# STM32F407VG.net
KiCad netlist of a schematic drawn in Altium Designer
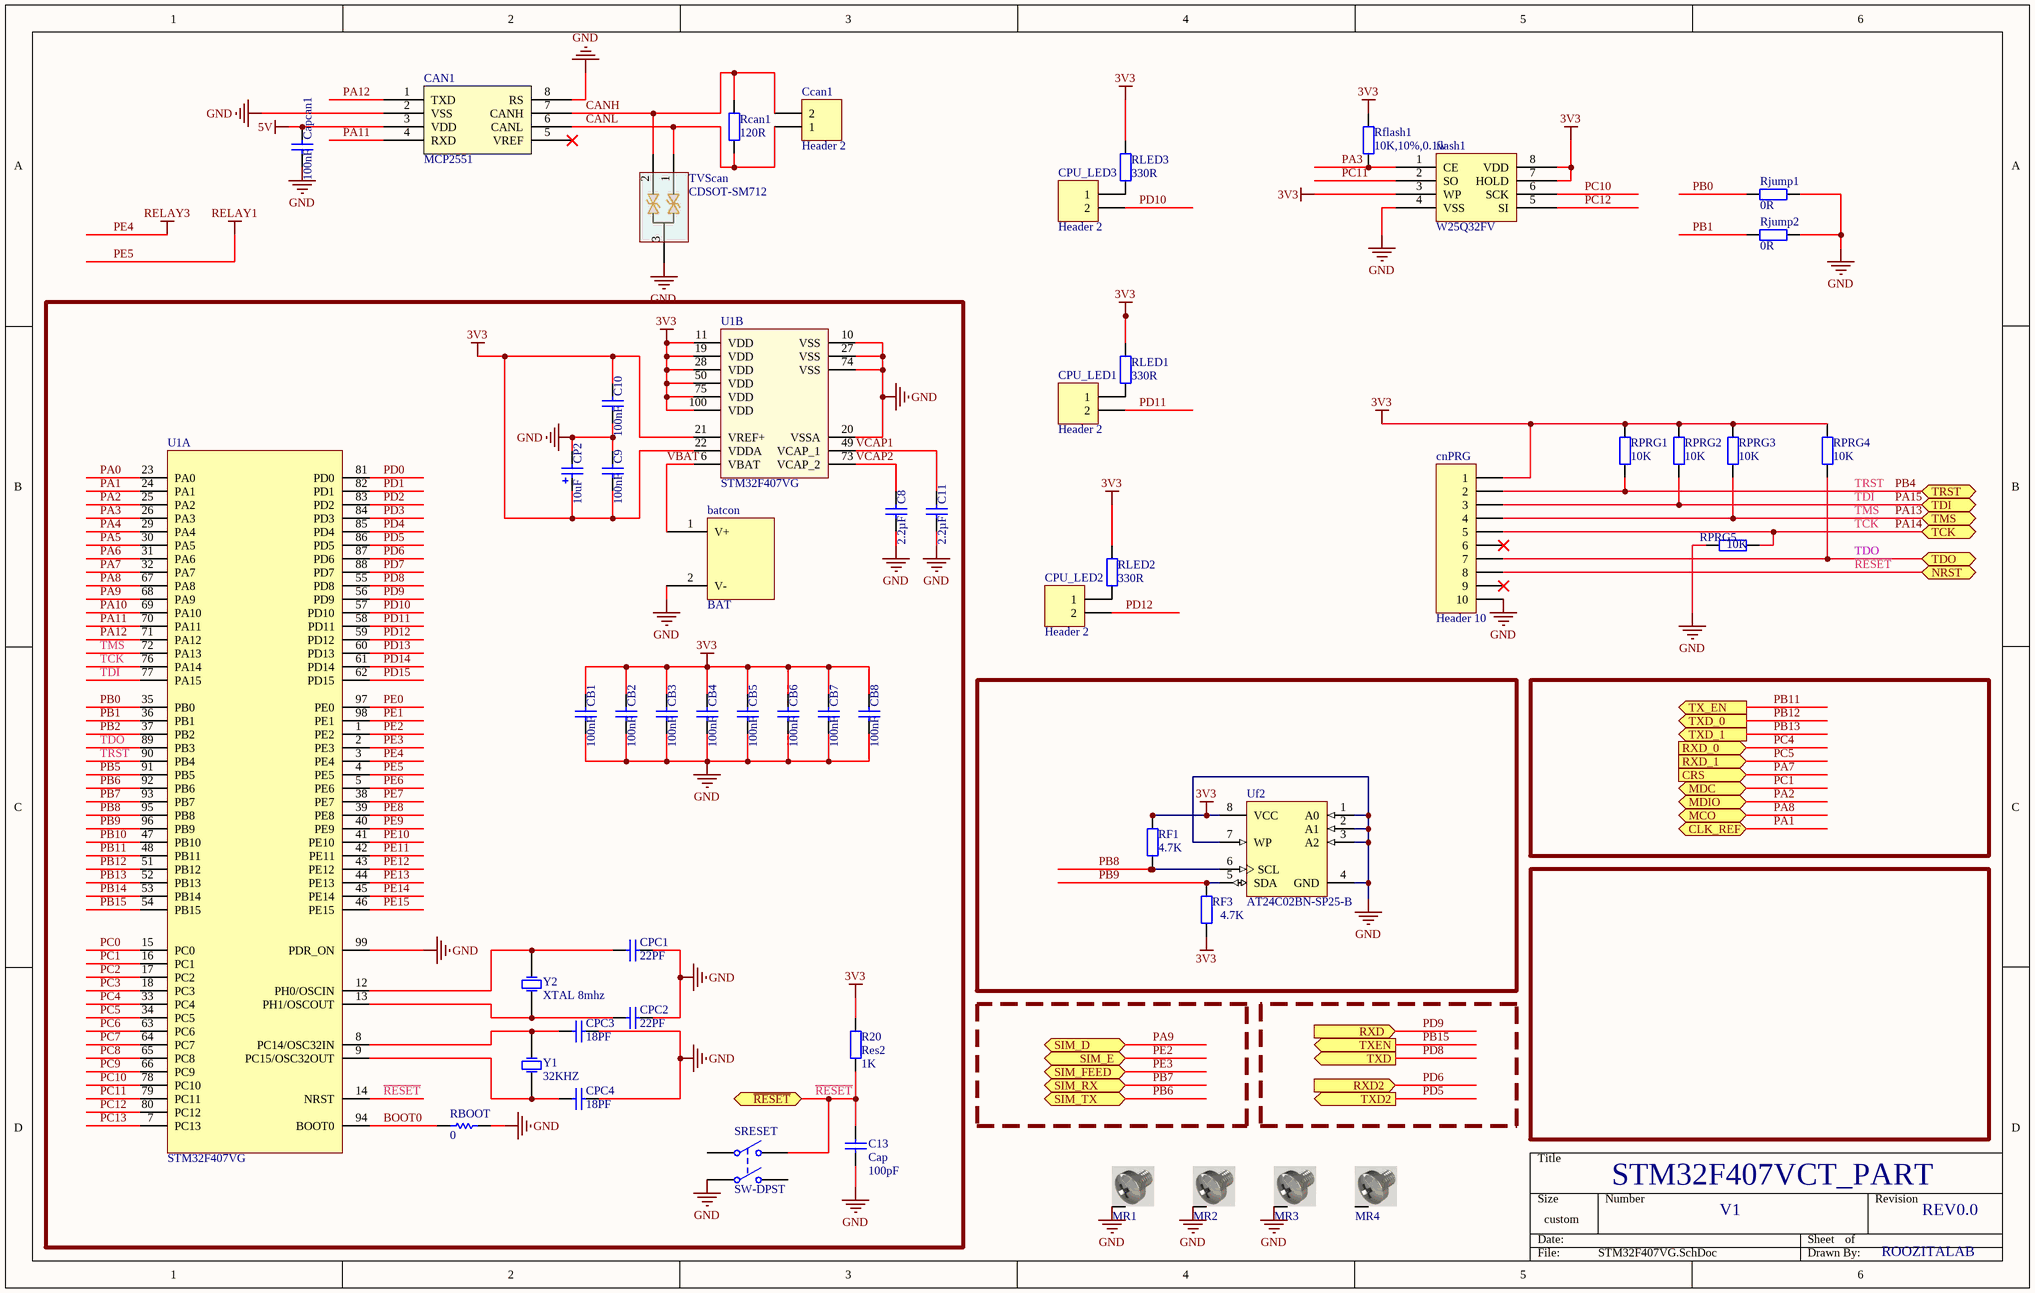
[diagram p0: STM32F407VG.SchDoc]

(export (version "E")
  (design (tool "Eeschema 10.0.6"))
  (components
    (comp (ref "batcon") (value "BAT") (footprint "BATTERY") (libsource (lib "my dxp lib") (part "BAT")))
    (comp (ref "C8")
      (value "2.2µF")
      (footprint "0805.")
      (description "Capacitor")
      (fields (field (name "PUBLISHER") "Altium Limited"))
      (libsource (lib "STM32F407_144") (part "Cap"))
    )
    (comp (ref "C9")
      (value "100nF")
      (footprint "0805.")
      (description "Capacitor")
      (fields (field (name "PUBLISHER") "Altium Limited"))
      (libsource (lib "STM32F407_144") (part "Cap"))
    )
    (comp (ref "C10")
      (value "100nF")
      (footprint "0805.")
      (description "Capacitor")
      (fields (field (name "PUBLISHER") "Altium Limited"))
      (libsource (lib "STM32F407_144") (part "Cap"))
    )
    (comp (ref "C11")
      (value "2.2µF")
      (footprint "0805.")
      (description "Capacitor")
      (fields (field (name "PUBLISHER") "Altium Limited"))
      (libsource (lib "STM32F407_144") (part "Cap"))
    )
    (comp (ref "C13")
      (value "Cap")
      (footprint "0805.")
      (description "Capacitor")
      (fields (field (name "ALTIUM_VALUE") "100pF") (field (name "PUBLISHER") "Altium Limited"))
      (libsource (lib "Miscellaneous Devices") (part "Cap"))
    )
    (comp (ref "CAN1")
      (value "MCP2551")
      (footprint "SOIC8")
      (libsource (lib "PCB_Project1") (part "SN65VHD230"))
    )
    (comp (ref "Capcan1")
      (value "100nF")
      (footprint "0805.")
      (description "Capacitor")
      (fields (field (name "PUBLISHER") "Altium Limited"))
      (libsource (lib "STM32F407_144") (part "Cap"))
    )
    (comp (ref "CB1")
      (value "100nF")
      (footprint "0805.")
      (description "Capacitor")
      (fields (field (name "PUBLISHER") "Altium Limited"))
      (libsource (lib "STM32F407_144") (part "Cap"))
    )
    (comp (ref "CB2")
      (value "100nF")
      (footprint "0805.")
      (description "Capacitor")
      (fields (field (name "PUBLISHER") "Altium Limited"))
      (libsource (lib "STM32F407_144") (part "Cap"))
    )
    (comp (ref "CB3")
      (value "100nF")
      (footprint "0805.")
      (description "Capacitor")
      (fields (field (name "PUBLISHER") "Altium Limited"))
      (libsource (lib "STM32F407_144") (part "Cap"))
    )
    (comp (ref "CB4")
      (value "100nF")
      (footprint "0805.")
      (description "Capacitor")
      (fields (field (name "PUBLISHER") "Altium Limited"))
      (libsource (lib "STM32F407_144") (part "Cap"))
    )
    (comp (ref "CB5")
      (value "100nF")
      (footprint "0805.")
      (description "Capacitor")
      (fields (field (name "PUBLISHER") "Altium Limited"))
      (libsource (lib "STM32F407_144") (part "Cap"))
    )
    (comp (ref "CB6")
      (value "100nF")
      (footprint "0805.")
      (description "Capacitor")
      (fields (field (name "PUBLISHER") "Altium Limited"))
      (libsource (lib "STM32F407_144") (part "Cap"))
    )
    (comp (ref "CB7")
      (value "100nF")
      (footprint "0805.")
      (description "Capacitor")
      (fields (field (name "PUBLISHER") "Altium Limited"))
      (libsource (lib "STM32F407_144") (part "Cap"))
    )
    (comp (ref "CB8")
      (value "100nF")
      (footprint "0805.")
      (description "Capacitor")
      (fields (field (name "PUBLISHER") "Altium Limited"))
      (libsource (lib "STM32F407_144") (part "Cap"))
    )
    (comp (ref "Ccan1")
      (value "Header 2")
      (footprint "HDR1X2")
      (description "Header, 2-Pin")
      (fields (field (name "PUBLISHER") "Altium Limited"))
      (libsource (lib "") (part "Header 2_1"))
    )
    (comp (ref "cnPRG")
      (value "Header 10")
      (footprint "HDR1X10")
      (description "Header, 10-Pin")
      (fields (field (name "PUBLISHER") "Altium Limited"))
      (libsource (lib "Miscellaneous Connectors") (part "Header 10"))
    )
    (comp (ref "CP2")
      (value "10uF")
      (footprint "C1206.")
      (description "Polarized Capacitor (Radial)")
      (fields (field (name "PUBLISHER") "Altium Limited"))
      (libsource (lib "STM32F407_144") (part "Cap Pol1"))
    )
    (comp (ref "CPC1")
      (value "22PF")
      (footprint "0805.")
      (description "Capacitor")
      (fields (field (name "PUBLISHER") "Altium Limited"))
      (libsource (lib "STM32F407VG") (part "Cap"))
    )
    (comp (ref "CPC2")
      (value "22PF")
      (footprint "0805.")
      (description "Capacitor")
      (fields (field (name "PUBLISHER") "Altium Limited"))
      (libsource (lib "STM32F407VG") (part "Cap"))
    )
    (comp (ref "CPC3")
      (value "18PF")
      (footprint "0805.")
      (description "Capacitor")
      (fields (field (name "PUBLISHER") "Altium Limited"))
      (libsource (lib "STM32F407VG") (part "Cap"))
    )
    (comp (ref "CPC4")
      (value "18PF")
      (footprint "0805.")
      (description "Capacitor")
      (fields (field (name "PUBLISHER") "Altium Limited"))
      (libsource (lib "STM32F407VG") (part "Cap"))
    )
    (comp (ref "CPU_LED1")
      (value "Header 2")
      (footprint "HDR1X2")
      (description "Header, 2-Pin")
      (fields (field (name "PUBLISHER") "Altium Limited"))
      (libsource (lib "Miscellaneous Connectors") (part "Header 2"))
    )
    (comp (ref "CPU_LED2")
      (value "Header 2")
      (footprint "HDR1X2")
      (description "Header, 2-Pin")
      (fields (field (name "PUBLISHER") "Altium Limited"))
      (libsource (lib "Miscellaneous Connectors") (part "Header 2"))
    )
    (comp (ref "CPU_LED3")
      (value "Header 2")
      (footprint "HDR1X2")
      (description "Header, 2-Pin")
      (fields (field (name "PUBLISHER") "Altium Limited"))
      (libsource (lib "Miscellaneous Connectors") (part "Header 2"))
    )
    (comp (ref "flash1")
      (value "W25Q32FV")
      (footprint "SOIC8")
      (libsource (lib "PCB_Project1") (part "SST25"))
    )
    (comp (ref "MR1")
      (value "Screw")
      (footprint "Board Screw")
      (description "Board Screw With Spacer")
      (libsource (lib "My Library") (part "Board Screw"))
    )
    (comp (ref "MR2")
      (value "Screw")
      (footprint "Board Screw")
      (description "Board Screw With Spacer")
      (libsource (lib "My Library") (part "Board Screw"))
    )
    (comp (ref "MR3")
      (value "Screw")
      (footprint "Board Screw")
      (description "Board Screw With Spacer")
      (libsource (lib "My Library") (part "Board Screw"))
    )
    (comp (ref "MR4")
      (value "Screw")
      (footprint "Board Screw")
      (description "Board Screw With Spacer")
      (libsource (lib "My Library") (part "Board Screw"))
    )
    (comp (ref "R20")
      (value "Res2")
      (footprint "0805.")
      (description "Resistor")
      (fields (field (name "ALTIUM_VALUE") "1K") (field (name "PUBLISHER") "Altium Limited"))
      (libsource (lib "Miscellaneous Devices") (part "Res2"))
    )
    (comp (ref "RBOOT")
      (value "0")
      (footprint "0805.")
      (description "Resistor")
      (fields (field (name "PUBLISHER") "Altium Limited"))
      (libsource (lib "STM32F407_144") (part "Res1"))
    )
    (comp (ref "Rcan1")
      (value "120R")
      (footprint "0805.")
      (description "Resistor")
      (fields (field (name "Comment") "120R,10%,0.1w") (field (name "PUBLISHER") "Altium Limited"))
      (libsource (lib "MBIO-SCHPCB-MBFD-REV1") (part "Res2"))
    )
    (comp (ref "RF1")
      (value "4.7K")
      (footprint "0805.")
      (description "Resistor")
      (fields (field (name "Comment") "Res2") (field (name "PUBLISHER") "Altium Limited"))
      (libsource (lib "") (part "Res2_1"))
    )
    (comp (ref "RF3")
      (value "4.7K")
      (footprint "0805.")
      (description "Resistor")
      (fields (field (name "Comment") "Res2") (field (name "PUBLISHER") "Altium Limited"))
      (libsource (lib "") (part "Res2_1"))
    )
    (comp (ref "Rflash1")
      (value "10K,10%,0.1w")
      (footprint "0805.")
      (description "Resistor")
      (fields (field (name "PUBLISHER") "Altium Limited"))
      (libsource (lib "") (part "Res2_1"))
    )
    (comp (ref "Rjump1")
      (value "0R")
      (footprint "0805.")
      (description "Resistor")
      (fields (field (name "Comment") "10K,10%,0.1w") (field (name "PUBLISHER") "Altium Limited"))
      (libsource (lib "PCB_Project1") (part "Res2"))
    )
    (comp (ref "Rjump2")
      (value "0R")
      (footprint "0805.")
      (description "Resistor")
      (fields (field (name "Comment") "10K,10%,0.1w") (field (name "PUBLISHER") "Altium Limited"))
      (libsource (lib "PCB_Project1") (part "Res2"))
    )
    (comp (ref "RLED1")
      (value "330R")
      (footprint "0805.")
      (description "Resistor")
      (fields (field (name "Comment") "330R,10%,0.1w") (field (name "PUBLISHER") "Altium Limited"))
      (libsource (lib "MBIO-SCHPCB-MBFD-REV1") (part "Res2"))
    )
    (comp (ref "RLED2")
      (value "330R")
      (footprint "0805.")
      (description "Resistor")
      (fields (field (name "Comment") "330R,10%,0.1w") (field (name "PUBLISHER") "Altium Limited"))
      (libsource (lib "MBIO-SCHPCB-MBFD-REV1") (part "Res2"))
    )
    (comp (ref "RLED3")
      (value "330R")
      (footprint "0805.")
      (description "Resistor")
      (fields (field (name "Comment") "330R,10%,0.1w") (field (name "PUBLISHER") "Altium Limited"))
      (libsource (lib "MBIO-SCHPCB-MBFD-REV1") (part "Res2"))
    )
    (comp (ref "RPRG1")
      (value "10K")
      (footprint "0805.")
      (description "Resistor")
      (fields (field (name "Comment") "Res2") (field (name "PUBLISHER") "Altium Limited"))
      (libsource (lib "") (part "Res2_1"))
    )
    (comp (ref "RPRG2")
      (value "10K")
      (footprint "0805.")
      (description "Resistor")
      (fields (field (name "Comment") "Res2") (field (name "PUBLISHER") "Altium Limited"))
      (libsource (lib "") (part "Res2_1"))
    )
    (comp (ref "RPRG3")
      (value "10K")
      (footprint "0805.")
      (description "Resistor")
      (fields (field (name "Comment") "Res2") (field (name "PUBLISHER") "Altium Limited"))
      (libsource (lib "") (part "Res2_1"))
    )
    (comp (ref "RPRG4")
      (value "10K")
      (footprint "0805.")
      (description "Resistor")
      (fields (field (name "Comment") "Res2") (field (name "PUBLISHER") "Altium Limited"))
      (libsource (lib "") (part "Res2_1"))
    )
    (comp (ref "RPRG5")
      (value "10K")
      (footprint "0805.")
      (description "Resistor")
      (fields (field (name "Comment") "Res2") (field (name "PUBLISHER") "Altium Limited"))
      (libsource (lib "") (part "Res2_2"))
    )
    (comp (ref "SRESET")
      (value "SW-DPST")
      (footprint "B3FS_SWITCH")
      (description "Double-Pole, Single-Throw Switch")
      (fields (field (name "PUBLISHER") "Altium Limited"))
      (libsource (lib "Miscellaneous Devices") (part "SW-DPST"))
    )
    (comp (ref "TVScan")
      (value "CDSOT-SM712")
      (footprint "2N3906_SMD")
      (libsource (lib "my schem") (part "nup2105"))
    )
    (comp (ref "U1")
      (value "STM32F407VG")
      (footprint "stm32f107")
      (libsource (lib "my dxp lib") (part "STM32F407VG"))
    )
    (comp (ref "Uf2")
      (value "AT24C02BN-SP25-B")
      (footprint "SOP8")
      (fields (field (name "PUBLISHER") "Altium Limited"))
      (libsource (lib "Atmel Memory Serial EEPROM") (part "AT24C02BN-SP25-B"))
    )
    (comp (ref "Y1")
      (value "32KHZ")
      (footprint "XTAL-RTC-RA")
      (description "Crystal Oscillator")
      (fields (field (name "PUBLISHER") "Altium Limited"))
      (libsource (lib "alarm box") (part "XTAL_1"))
    )
    (comp (ref "Y2")
      (value "XTAL 8mhz")
      (footprint "XTAL Small")
      (description "Crystal Oscillator")
      (fields (field (name "PUBLISHER") "Altium Limited"))
      (libsource (lib "alarm box") (part "XTAL"))
    )
  )
  (nets
    (net (code "1") (name "/BOOT0") (class "Default")
      (node (ref "RBOOT") (pin "1") (pinfunction "1_1") (pintype "passive"))
      (node (ref "U1") (pin "94") (pinfunction "BOOT0_94") (pintype "passive"))
    )
    (net (code "2") (name "/CANH") (class "Default")
      (node (ref "CAN1") (pin "7") (pinfunction "CANH_7") (pintype "passive"))
      (node (ref "Ccan1") (pin "2") (pinfunction "2_2") (pintype "passive"))
      (node (ref "Rcan1") (pin "2") (pinfunction "2_2") (pintype "passive"))
      (node (ref "TVScan") (pin "2") (pinfunction "2_2") (pintype "passive"))
    )
    (net (code "3") (name "/CANL") (class "Default")
      (node (ref "CAN1") (pin "6") (pinfunction "CANL_6") (pintype "passive"))
      (node (ref "Ccan1") (pin "1") (pinfunction "1_1") (pintype "passive"))
      (node (ref "Rcan1") (pin "1") (pinfunction "1_1") (pintype "passive"))
      (node (ref "TVScan") (pin "1") (pinfunction "1_1") (pintype "passive"))
    )
    (net (code "4") (name "/PA0") (class "Default")
      (node (ref "U1") (pin "23") (pinfunction "PA0_23") (pintype "passive"))
    )
    (net (code "5") (name "/PA1") (class "Default")
      (node (ref "U1") (pin "24") (pinfunction "PA1_24") (pintype "passive"))
    )
    (net (code "6") (name "/PA2") (class "Default")
      (node (ref "U1") (pin "25") (pinfunction "PA2_25") (pintype "passive"))
    )
    (net (code "7") (name "/PA3") (class "Default")
      (node (ref "Rflash1") (pin "2") (pinfunction "2_2") (pintype "passive"))
      (node (ref "U1") (pin "26") (pinfunction "PA3_26") (pintype "passive"))
      (node (ref "flash1") (pin "1") (pinfunction "CE_1") (pintype "passive"))
    )
    (net (code "8") (name "/PA4") (class "Default")
      (node (ref "U1") (pin "29") (pinfunction "PA4_29") (pintype "passive"))
    )
    (net (code "9") (name "/PA5") (class "Default")
      (node (ref "U1") (pin "30") (pinfunction "PA5_30") (pintype "passive"))
    )
    (net (code "10") (name "/PA6") (class "Default")
      (node (ref "U1") (pin "31") (pinfunction "PA6_31") (pintype "passive"))
    )
    (net (code "11") (name "/PA7") (class "Default")
      (node (ref "U1") (pin "32") (pinfunction "PA7_32") (pintype "passive"))
    )
    (net (code "12") (name "/PA8") (class "Default")
      (node (ref "U1") (pin "67") (pinfunction "PA8_67") (pintype "passive"))
    )
    (net (code "13") (name "/PA9") (class "Default")
      (node (ref "U1") (pin "68") (pinfunction "PA9_68") (pintype "passive"))
    )
    (net (code "14") (name "/PA10") (class "Default")
      (node (ref "U1") (pin "69") (pinfunction "PA10_69") (pintype "passive"))
    )
    (net (code "15") (name "/PA11") (class "Default")
      (node (ref "CAN1") (pin "4") (pinfunction "RXD_4") (pintype "passive"))
      (node (ref "U1") (pin "70") (pinfunction "PA11_70") (pintype "passive"))
    )
    (net (code "16") (name "/PA12") (class "Default")
      (node (ref "CAN1") (pin "1") (pinfunction "TXD_1") (pintype "passive"))
      (node (ref "U1") (pin "71") (pinfunction "PA12_71") (pintype "passive"))
    )
    (net (code "17") (name "/PA13") (class "Default")
      (node (ref "RPRG3") (pin "2") (pinfunction "2_2") (pintype "passive"))
      (node (ref "U1") (pin "72") (pinfunction "PA13_72") (pintype "passive"))
      (node (ref "cnPRG") (pin "4") (pinfunction "4_4") (pintype "passive"))
    )
    (net (code "18") (name "/PA14") (class "Default")
      (node (ref "RPRG5") (pin "1") (pinfunction "1_1") (pintype "passive"))
      (node (ref "U1") (pin "76") (pinfunction "PA14_76") (pintype "passive"))
      (node (ref "cnPRG") (pin "5") (pinfunction "5_5") (pintype "passive"))
    )
    (net (code "19") (name "/PA15") (class "Default")
      (node (ref "RPRG2") (pin "2") (pinfunction "2_2") (pintype "passive"))
      (node (ref "U1") (pin "77") (pinfunction "PA15_77") (pintype "passive"))
      (node (ref "cnPRG") (pin "3") (pinfunction "3_3") (pintype "passive"))
    )
    (net (code "20") (name "/PB0") (class "Default")
      (node (ref "Rjump1") (pin "1") (pinfunction "1_1") (pintype "passive"))
      (node (ref "U1") (pin "35") (pinfunction "PB0_35") (pintype "passive"))
    )
    (net (code "21") (name "/PB1") (class "Default")
      (node (ref "Rjump2") (pin "1") (pinfunction "1_1") (pintype "passive"))
      (node (ref "U1") (pin "36") (pinfunction "PB1_36") (pintype "passive"))
    )
    (net (code "22") (name "/PB2") (class "Default")
      (node (ref "U1") (pin "37") (pinfunction "PB2_37") (pintype "passive"))
    )
    (net (code "23") (name "/PB4") (class "Default")
      (node (ref "RPRG1") (pin "2") (pinfunction "2_2") (pintype "passive"))
      (node (ref "U1") (pin "90") (pinfunction "PB4_90") (pintype "passive"))
      (node (ref "cnPRG") (pin "2") (pinfunction "2_2") (pintype "passive"))
    )
    (net (code "24") (name "/PB5") (class "Default")
      (node (ref "U1") (pin "91") (pinfunction "PB5_91") (pintype "passive"))
    )
    (net (code "25") (name "/PB6") (class "Default")
      (node (ref "U1") (pin "92") (pinfunction "PB6_92") (pintype "passive"))
    )
    (net (code "26") (name "/PB7") (class "Default")
      (node (ref "U1") (pin "93") (pinfunction "PB7_93") (pintype "passive"))
    )
    (net (code "27") (name "/PB8") (class "Default")
      (node (ref "RF1") (pin "2") (pinfunction "2_2") (pintype "passive"))
      (node (ref "U1") (pin "95") (pinfunction "PB8_95") (pintype "passive"))
      (node (ref "Uf2") (pin "6") (pinfunction "SCL_6") (pintype "input"))
    )
    (net (code "28") (name "/PB9") (class "Default")
      (node (ref "RF3") (pin "1") (pinfunction "1_1") (pintype "passive"))
      (node (ref "U1") (pin "96") (pinfunction "PB9_96") (pintype "passive"))
      (node (ref "Uf2") (pin "5") (pinfunction "SDA_5") (pintype "bidirectional"))
    )
    (net (code "29") (name "/PB10") (class "Default")
      (node (ref "U1") (pin "47") (pinfunction "PB10_47") (pintype "passive"))
    )
    (net (code "30") (name "/PB11") (class "Default")
      (node (ref "U1") (pin "48") (pinfunction "PB11_48") (pintype "passive"))
    )
    (net (code "31") (name "/PB12") (class "Default")
      (node (ref "U1") (pin "51") (pinfunction "PB12_51") (pintype "passive"))
    )
    (net (code "32") (name "/PB13") (class "Default")
      (node (ref "U1") (pin "52") (pinfunction "PB13_52") (pintype "passive"))
    )
    (net (code "33") (name "/PB14") (class "Default")
      (node (ref "U1") (pin "53") (pinfunction "PB14_53") (pintype "passive"))
    )
    (net (code "34") (name "/PB15") (class "Default")
      (node (ref "U1") (pin "54") (pinfunction "PB15_54") (pintype "passive"))
    )
    (net (code "35") (name "/PC0") (class "Default")
      (node (ref "U1") (pin "15") (pinfunction "PC0_15") (pintype "passive"))
    )
    (net (code "36") (name "/PC1") (class "Default")
      (node (ref "U1") (pin "16") (pinfunction "PC1_16") (pintype "passive"))
    )
    (net (code "37") (name "/PC2") (class "Default")
      (node (ref "U1") (pin "17") (pinfunction "PC2_17") (pintype "passive"))
    )
    (net (code "38") (name "/PC3") (class "Default")
      (node (ref "U1") (pin "18") (pinfunction "PC3_18") (pintype "passive"))
    )
    (net (code "39") (name "/PC4") (class "Default")
      (node (ref "U1") (pin "33") (pinfunction "PC4_33") (pintype "passive"))
    )
    (net (code "40") (name "/PC5") (class "Default")
      (node (ref "U1") (pin "34") (pinfunction "PC5_34") (pintype "passive"))
    )
    (net (code "41") (name "/PC6") (class "Default")
      (node (ref "U1") (pin "63") (pinfunction "PC6_63") (pintype "passive"))
    )
    (net (code "42") (name "/PC7") (class "Default")
      (node (ref "U1") (pin "64") (pinfunction "PC7_64") (pintype "passive"))
    )
    (net (code "43") (name "/PC8") (class "Default")
      (node (ref "U1") (pin "65") (pinfunction "PC8_65") (pintype "passive"))
    )
    (net (code "44") (name "/PC9") (class "Default")
      (node (ref "U1") (pin "66") (pinfunction "PC9_66") (pintype "passive"))
    )
    (net (code "45") (name "/PC10") (class "Default")
      (node (ref "U1") (pin "78") (pinfunction "PC10_78") (pintype "passive"))
      (node (ref "flash1") (pin "6") (pinfunction "SCK_6") (pintype "passive"))
    )
    (net (code "46") (name "/PC11") (class "Default")
      (node (ref "U1") (pin "79") (pinfunction "PC11_79") (pintype "passive"))
      (node (ref "flash1") (pin "2") (pinfunction "SO_2") (pintype "passive"))
    )
    (net (code "47") (name "/PC12") (class "Default")
      (node (ref "U1") (pin "80") (pinfunction "PC12_80") (pintype "passive"))
      (node (ref "flash1") (pin "5") (pinfunction "SI_5") (pintype "passive"))
    )
    (net (code "48") (name "/PC13") (class "Default")
      (node (ref "U1") (pin "7") (pinfunction "PC13_7") (pintype "passive"))
    )
    (net (code "49") (name "/PD0") (class "Default")
      (node (ref "U1") (pin "81") (pinfunction "PD0_81") (pintype "passive"))
    )
    (net (code "50") (name "/PD1") (class "Default")
      (node (ref "U1") (pin "82") (pinfunction "PD1_82") (pintype "passive"))
    )
    (net (code "51") (name "/PD2") (class "Default")
      (node (ref "U1") (pin "83") (pinfunction "PD2_83") (pintype "passive"))
    )
    (net (code "52") (name "/PD3") (class "Default")
      (node (ref "U1") (pin "84") (pinfunction "PD3_84") (pintype "passive"))
    )
    (net (code "53") (name "/PD4") (class "Default")
      (node (ref "U1") (pin "85") (pinfunction "PD4_85") (pintype "passive"))
    )
    (net (code "54") (name "/PD5") (class "Default")
      (node (ref "U1") (pin "86") (pinfunction "PD5_86") (pintype "passive"))
    )
    (net (code "55") (name "/PD6") (class "Default")
      (node (ref "U1") (pin "87") (pinfunction "PD6_87") (pintype "passive"))
    )
    (net (code "56") (name "/PD7") (class "Default")
      (node (ref "U1") (pin "88") (pinfunction "PD7_88") (pintype "passive"))
    )
    (net (code "57") (name "/PD8") (class "Default")
      (node (ref "U1") (pin "55") (pinfunction "PD8_55") (pintype "passive"))
    )
    (net (code "58") (name "/PD9") (class "Default")
      (node (ref "U1") (pin "56") (pinfunction "PD9_56") (pintype "passive"))
    )
    (net (code "59") (name "/PD10") (class "Default")
      (node (ref "CPU_LED3") (pin "2") (pinfunction "2_2") (pintype "passive"))
      (node (ref "U1") (pin "57") (pinfunction "PD10_57") (pintype "passive"))
    )
    (net (code "60") (name "/PD11") (class "Default")
      (node (ref "CPU_LED1") (pin "2") (pinfunction "2_2") (pintype "passive"))
      (node (ref "U1") (pin "58") (pinfunction "PD11_58") (pintype "passive"))
    )
    (net (code "61") (name "/PD12") (class "Default")
      (node (ref "CPU_LED2") (pin "2") (pinfunction "2_2") (pintype "passive"))
      (node (ref "U1") (pin "59") (pinfunction "PD12_59") (pintype "passive"))
    )
    (net (code "62") (name "/PD13") (class "Default")
      (node (ref "U1") (pin "60") (pinfunction "PD13_60") (pintype "passive"))
    )
    (net (code "63") (name "/PD14") (class "Default")
      (node (ref "U1") (pin "61") (pinfunction "PD14_61") (pintype "passive"))
    )
    (net (code "64") (name "/PD15") (class "Default")
      (node (ref "U1") (pin "62") (pinfunction "PD15_62") (pintype "passive"))
    )
    (net (code "65") (name "/PE0") (class "Default")
      (node (ref "U1") (pin "97") (pinfunction "PE0_97") (pintype "passive"))
    )
    (net (code "66") (name "/PE1") (class "Default")
      (node (ref "U1") (pin "98") (pinfunction "PE1_98") (pintype "passive"))
    )
    (net (code "67") (name "/PE2") (class "Default")
      (node (ref "U1") (pin "1") (pinfunction "PE2_1") (pintype "passive"))
    )
    (net (code "68") (name "/PE3") (class "Default")
      (node (ref "U1") (pin "2") (pinfunction "PE3_2") (pintype "passive"))
    )
    (net (code "69") (name "/PE6") (class "Default")
      (node (ref "U1") (pin "5") (pinfunction "PE6_5") (pintype "passive"))
    )
    (net (code "70") (name "/PE7") (class "Default")
      (node (ref "U1") (pin "38") (pinfunction "PE7_38") (pintype "passive"))
    )
    (net (code "71") (name "/PE8") (class "Default")
      (node (ref "U1") (pin "39") (pinfunction "PE8_39") (pintype "passive"))
    )
    (net (code "72") (name "/PE9") (class "Default")
      (node (ref "U1") (pin "40") (pinfunction "PE9_40") (pintype "passive"))
    )
    (net (code "73") (name "/PE10") (class "Default")
      (node (ref "U1") (pin "41") (pinfunction "PE10_41") (pintype "passive"))
    )
    (net (code "74") (name "/PE11") (class "Default")
      (node (ref "U1") (pin "42") (pinfunction "PE11_42") (pintype "passive"))
    )
    (net (code "75") (name "/PE12") (class "Default")
      (node (ref "U1") (pin "43") (pinfunction "PE12_43") (pintype "passive"))
    )
    (net (code "76") (name "/PE13") (class "Default")
      (node (ref "U1") (pin "44") (pinfunction "PE13_44") (pintype "passive"))
    )
    (net (code "77") (name "/PE14") (class "Default")
      (node (ref "U1") (pin "45") (pinfunction "PE14_45") (pintype "passive"))
    )
    (net (code "78") (name "/PE15") (class "Default")
      (node (ref "U1") (pin "46") (pinfunction "PE15_46") (pintype "passive"))
    )
    (net (code "79") (name "/TDO") (class "Default")
      (node (ref "RPRG4") (pin "2") (pinfunction "2_2") (pintype "passive"))
      (node (ref "U1") (pin "89") (pinfunction "PB3_89") (pintype "passive"))
      (node (ref "cnPRG") (pin "7") (pinfunction "7_7") (pintype "passive"))
    )
    (net (code "80") (name "/VBAT") (class "Default")
      (node (ref "U1") (pin "6") (pinfunction "VBAT_6") (pintype "passive"))
      (node (ref "batcon") (pin "1") (pinfunction "V+_1") (pintype "passive"))
    )
    (net (code "81") (name "/VCAP1") (class "Default")
      (node (ref "C11") (pin "2") (pinfunction "2_2") (pintype "passive"))
      (node (ref "U1") (pin "49") (pinfunction "VCAP_1_49") (pintype "passive"))
    )
    (net (code "82") (name "/VCAP2") (class "Default")
      (node (ref "C8") (pin "2") (pinfunction "2_2") (pintype "passive"))
      (node (ref "U1") (pin "73") (pinfunction "VCAP_2_73") (pintype "passive"))
    )
    (net (code "83") (name "/~{RESET}") (class "Default")
      (node (ref "C13") (pin "2") (pinfunction "2_2") (pintype "passive"))
      (node (ref "R20") (pin "1") (pinfunction "1_1") (pintype "passive"))
      (node (ref "SRESET") (pin "2") (pinfunction "NO1_2") (pintype "passive"))
      (node (ref "U1") (pin "14") (pinfunction "NRST_14") (pintype "passive"))
      (node (ref "cnPRG") (pin "8") (pinfunction "8_8") (pintype "passive"))
    )
    (net (code "84") (name "3V3") (class "Default")
      (node (ref "C10") (pin "2") (pinfunction "2_2") (pintype "passive"))
      (node (ref "C9") (pin "1") (pinfunction "1_1") (pintype "passive"))
      (node (ref "CB1") (pin "2") (pinfunction "2_2") (pintype "passive"))
      (node (ref "CB2") (pin "2") (pinfunction "2_2") (pintype "passive"))
      (node (ref "CB3") (pin "2") (pinfunction "2_2") (pintype "passive"))
      (node (ref "CB4") (pin "2") (pinfunction "2_2") (pintype "passive"))
      (node (ref "CB5") (pin "2") (pinfunction "2_2") (pintype "passive"))
      (node (ref "CB6") (pin "2") (pinfunction "2_2") (pintype "passive"))
      (node (ref "CB7") (pin "2") (pinfunction "2_2") (pintype "passive"))
      (node (ref "CB8") (pin "2") (pinfunction "2_2") (pintype "passive"))
      (node (ref "CP2") (pin "1") (pinfunction "1_1") (pintype "passive"))
      (node (ref "R20") (pin "2") (pinfunction "2_2") (pintype "passive"))
      (node (ref "RF1") (pin "1") (pinfunction "1_1") (pintype "passive"))
      (node (ref "RF3") (pin "2") (pinfunction "2_2") (pintype "passive"))
      (node (ref "RLED1") (pin "2") (pinfunction "2_2") (pintype "passive"))
      (node (ref "RLED2") (pin "2") (pinfunction "2_2") (pintype "passive"))
      (node (ref "RLED3") (pin "2") (pinfunction "2_2") (pintype "passive"))
      (node (ref "RPRG1") (pin "1") (pinfunction "1_1") (pintype "passive"))
      (node (ref "RPRG2") (pin "1") (pinfunction "1_1") (pintype "passive"))
      (node (ref "RPRG3") (pin "1") (pinfunction "1_1") (pintype "passive"))
      (node (ref "RPRG4") (pin "1") (pinfunction "1_1") (pintype "passive"))
      (node (ref "Rflash1") (pin "1") (pinfunction "1_1") (pintype "passive"))
      (node (ref "U1") (pin "100") (pinfunction "VDD_100") (pintype "passive"))
      (node (ref "U1") (pin "11") (pinfunction "VDD_11") (pintype "passive"))
      (node (ref "U1") (pin "19") (pinfunction "VDD_19") (pintype "passive"))
      (node (ref "U1") (pin "21") (pinfunction "VREF+_21") (pintype "passive"))
      (node (ref "U1") (pin "22") (pinfunction "VDDA_22") (pintype "passive"))
      (node (ref "U1") (pin "28") (pinfunction "VDD_28") (pintype "passive"))
      (node (ref "U1") (pin "50") (pinfunction "VDD_50") (pintype "passive"))
      (node (ref "U1") (pin "75") (pinfunction "VDD_75") (pintype "passive"))
      (node (ref "Uf2") (pin "8") (pinfunction "VCC_8") (pintype "power_in"))
      (node (ref "cnPRG") (pin "1") (pinfunction "1_1") (pintype "passive"))
      (node (ref "flash1") (pin "3") (pinfunction "WP_3") (pintype "passive"))
      (node (ref "flash1") (pin "7") (pinfunction "HOLD_7") (pintype "passive"))
      (node (ref "flash1") (pin "8") (pinfunction "VDD_8") (pintype "passive"))
    )
    (net (code "85") (name "5V") (class "Default")
      (node (ref "CAN1") (pin "3") (pinfunction "VDD_3") (pintype "passive"))
      (node (ref "Capcan1") (pin "2") (pinfunction "2_2") (pintype "passive"))
    )
    (net (code "86") (name "GND") (class "Default")
      (node (ref "C10") (pin "1") (pinfunction "1_1") (pintype "passive"))
      (node (ref "C11") (pin "1") (pinfunction "1_1") (pintype "passive"))
      (node (ref "C13") (pin "1") (pinfunction "1_1") (pintype "passive"))
      (node (ref "C8") (pin "1") (pinfunction "1_1") (pintype "passive"))
      (node (ref "C9") (pin "2") (pinfunction "2_2") (pintype "passive"))
      (node (ref "CAN1") (pin "2") (pinfunction "VSS_2") (pintype "passive"))
      (node (ref "CAN1") (pin "8") (pinfunction "RS_8") (pintype "passive"))
      (node (ref "CB1") (pin "1") (pinfunction "1_1") (pintype "passive"))
      (node (ref "CB2") (pin "1") (pinfunction "1_1") (pintype "passive"))
      (node (ref "CB3") (pin "1") (pinfunction "1_1") (pintype "passive"))
      (node (ref "CB4") (pin "1") (pinfunction "1_1") (pintype "passive"))
      (node (ref "CB5") (pin "1") (pinfunction "1_1") (pintype "passive"))
      (node (ref "CB6") (pin "1") (pinfunction "1_1") (pintype "passive"))
      (node (ref "CB7") (pin "1") (pinfunction "1_1") (pintype "passive"))
      (node (ref "CB8") (pin "1") (pinfunction "1_1") (pintype "passive"))
      (node (ref "CP2") (pin "2") (pinfunction "2_2") (pintype "passive"))
      (node (ref "CPC1") (pin "2") (pinfunction "2_2") (pintype "passive"))
      (node (ref "CPC2") (pin "2") (pinfunction "2_2") (pintype "passive"))
      (node (ref "CPC3") (pin "2") (pinfunction "2_2") (pintype "passive"))
      (node (ref "CPC4") (pin "2") (pinfunction "2_2") (pintype "passive"))
      (node (ref "Capcan1") (pin "1") (pinfunction "1_1") (pintype "passive"))
      (node (ref "MR1") (pin "S") (pinfunction "S_S") (pintype "passive"))
      (node (ref "MR2") (pin "S") (pinfunction "S_S") (pintype "passive"))
      (node (ref "MR3") (pin "S") (pinfunction "S_S") (pintype "passive"))
      (node (ref "RBOOT") (pin "2") (pinfunction "2_2") (pintype "passive"))
      (node (ref "RPRG5") (pin "2") (pinfunction "2_2") (pintype "passive"))
      (node (ref "Rjump1") (pin "2") (pinfunction "2_2") (pintype "passive"))
      (node (ref "Rjump2") (pin "2") (pinfunction "2_2") (pintype "passive"))
      (node (ref "SRESET") (pin "3") (pinfunction "COMMON2_3") (pintype "passive"))
      (node (ref "TVScan") (pin "3") (pinfunction "3_3") (pintype "passive"))
      (node (ref "U1") (pin "10") (pinfunction "VSS_10") (pintype "passive"))
      (node (ref "U1") (pin "20") (pinfunction "VSSA_20") (pintype "passive"))
      (node (ref "U1") (pin "27") (pinfunction "VSS_27") (pintype "passive"))
      (node (ref "U1") (pin "74") (pinfunction "VSS_74") (pintype "passive"))
      (node (ref "U1") (pin "99") (pinfunction "PDR_ON_99") (pintype "passive"))
      (node (ref "Uf2") (pin "1") (pinfunction "A0_1") (pintype "input"))
      (node (ref "Uf2") (pin "2") (pinfunction "A1_2") (pintype "input"))
      (node (ref "Uf2") (pin "3") (pinfunction "A2_3") (pintype "input"))
      (node (ref "Uf2") (pin "4") (pinfunction "GND_4") (pintype "power_in"))
      (node (ref "Uf2") (pin "7") (pinfunction "WP_7") (pintype "input"))
      (node (ref "batcon") (pin "2") (pinfunction "V-_2") (pintype "passive"))
      (node (ref "cnPRG") (pin "10") (pinfunction "10_10") (pintype "passive"))
      (node (ref "flash1") (pin "4") (pinfunction "VSS_4") (pintype "passive"))
    )
    (net (code "87") (name "Net-(CPU_LED1-Pad1)") (class "Default")
      (node (ref "CPU_LED1") (pin "1") (pinfunction "1_1") (pintype "passive"))
      (node (ref "RLED1") (pin "1") (pinfunction "1_1") (pintype "passive"))
    )
    (net (code "88") (name "Net-(CPU_LED2-Pad1)") (class "Default")
      (node (ref "CPU_LED2") (pin "1") (pinfunction "1_1") (pintype "passive"))
      (node (ref "RLED2") (pin "1") (pinfunction "1_1") (pintype "passive"))
    )
    (net (code "89") (name "Net-(CPU_LED3-Pad1)") (class "Default")
      (node (ref "CPU_LED3") (pin "1") (pinfunction "1_1") (pintype "passive"))
      (node (ref "RLED3") (pin "1") (pinfunction "1_1") (pintype "passive"))
    )
    (net (code "90") (name "Net-(U1A-PC14{slash}OSC32IN)") (class "Default")
      (node (ref "CPC3") (pin "1") (pinfunction "1_1") (pintype "passive"))
      (node (ref "U1") (pin "8") (pinfunction "PC14/OSC32IN_8") (pintype "passive"))
      (node (ref "Y1") (pin "2") (pinfunction "OSC2_2") (pintype "passive"))
    )
    (net (code "91") (name "Net-(U1A-PC15{slash}OSC32OUT)") (class "Default")
      (node (ref "CPC4") (pin "1") (pinfunction "1_1") (pintype "passive"))
      (node (ref "U1") (pin "9") (pinfunction "PC15/OSC32OUT_9") (pintype "passive"))
      (node (ref "Y1") (pin "1") (pinfunction "OSC1_1") (pintype "passive"))
    )
    (net (code "92") (name "Net-(U1A-PH0{slash}OSCIN)") (class "Default")
      (node (ref "CPC1") (pin "1") (pinfunction "1_1") (pintype "passive"))
      (node (ref "U1") (pin "12") (pinfunction "PH0/OSCIN_12") (pintype "passive"))
      (node (ref "Y2") (pin "2") (pinfunction "OSC2_2") (pintype "passive"))
    )
    (net (code "93") (name "Net-(U1A-PH1{slash}OSCOUT)") (class "Default")
      (node (ref "CPC2") (pin "1") (pinfunction "1_1") (pintype "passive"))
      (node (ref "U1") (pin "13") (pinfunction "PH1/OSCOUT_13") (pintype "passive"))
      (node (ref "Y2") (pin "1") (pinfunction "OSC1_1") (pintype "passive"))
    )
    (net (code "94") (name "RELAY1") (class "Default")
      (node (ref "U1") (pin "4") (pinfunction "PE5_4") (pintype "passive"))
    )
    (net (code "95") (name "RELAY3") (class "Default")
      (node (ref "U1") (pin "3") (pinfunction "PE4_3") (pintype "passive"))
    )
    (net (code "96") (name "unconnected-(CAN1-VREF-Pad5)") (class "Default")
      (node (ref "CAN1") (pin "5") (pinfunction "VREF_5") (pintype "passive+no_connect"))
    )
    (net (code "97") (name "unconnected-(MR4-PadS)") (class "Default")
      (node (ref "MR4") (pin "S") (pinfunction "S_S") (pintype "passive"))
    )
    (net (code "98") (name "unconnected-(SRESET-COMMON1-Pad1)") (class "Default")
      (node (ref "SRESET") (pin "1") (pinfunction "COMMON1_1") (pintype "passive"))
    )
    (net (code "99") (name "unconnected-(SRESET-NO2-Pad4)") (class "Default")
      (node (ref "SRESET") (pin "4") (pinfunction "NO2_4") (pintype "passive"))
    )
    (net (code "100") (name "unconnected-(cnPRG-Pad6)") (class "Default")
      (node (ref "cnPRG") (pin "6") (pinfunction "6_6") (pintype "passive+no_connect"))
    )
    (net (code "101") (name "unconnected-(cnPRG-Pad9)") (class "Default")
      (node (ref "cnPRG") (pin "9") (pinfunction "9_9") (pintype "passive+no_connect"))
    )
  )
)
